# Servorino_FT230X_brick_super_tiny.net
KiCad netlist of a schematic drawn in EAGLE
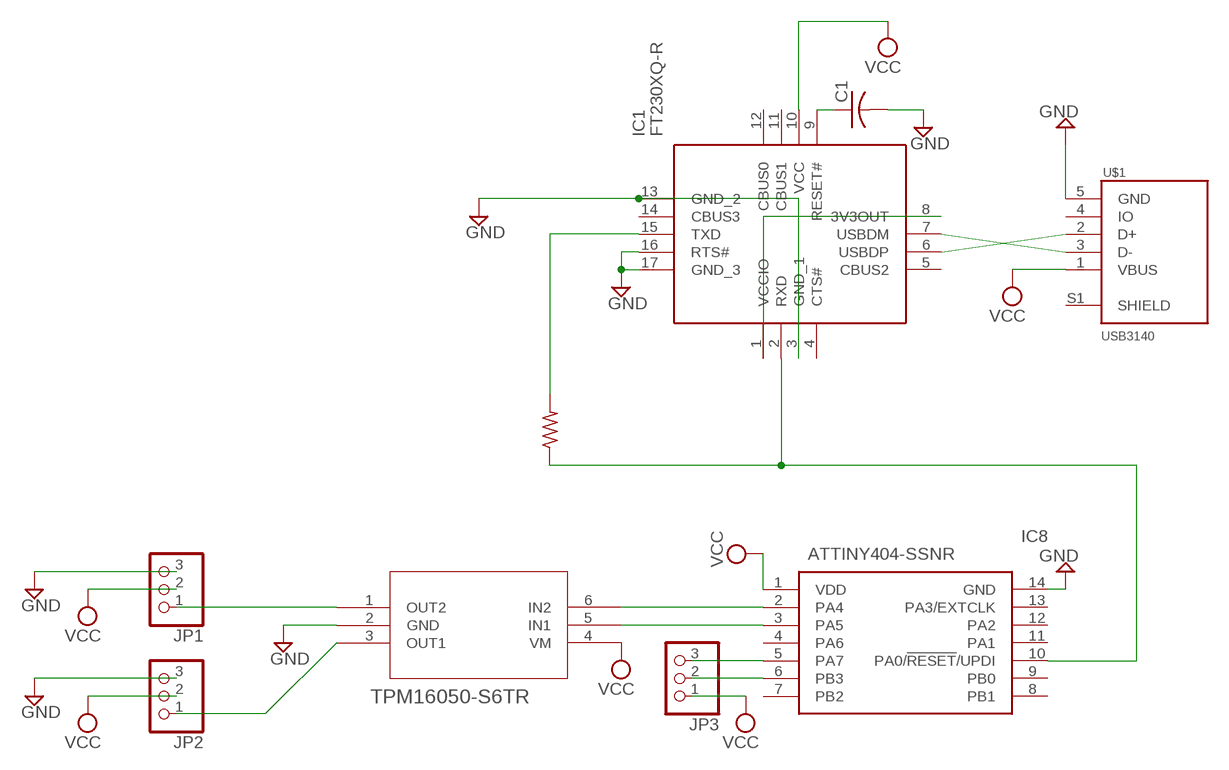
[diagram p0: schematic, sheet 1]

(export (version "E")
  (design (tool "Eeschema 10.0.6"))
  (components
    (comp (ref "C1")
      (value "C-USC0603")
      (footprint "eagle-import:C0603")
      (libsource (lib "eagle-import") (part "C-USC0603"))
    )
    (comp (ref "IC1")
      (value "FT230XQ-R")
      (footprint "eagle-import:QFN65P400X400X80-17N")
      (fields (field (name "MOUSER_PART_NUMBER") "895-FT230XQ-R"))
      (libsource (lib "eagle-import") (part "FT230XQ-R"))
    )
    (comp (ref "IC8")
      (value "ATTINY404-SSNR")
      (footprint "eagle-import:SOIC127P600X175-14N")
      (fields (field (name "MOUSER_PART_NUMBER") "556-ATTINY404-SSNR"))
      (libsource (lib "eagle-import") (part "ATTINY404-SSNR"))
    )
    (comp (ref "JP1")
      (value "PINHD-1X3")
      (footprint "eagle-import:1X03")
      (libsource (lib "eagle-import") (part "PINHD-1X3"))
    )
    (comp (ref "JP2")
      (value "PINHD-1X3")
      (footprint "eagle-import:1X03")
      (libsource (lib "eagle-import") (part "PINHD-1X3"))
    )
    (comp (ref "JP3")
      (value "PINHD-1X3")
      (footprint "eagle-import:1X03")
      (libsource (lib "eagle-import") (part "PINHD-1X3"))
    )
    (comp (ref "R6")
      (value "470")
      (footprint "eagle-import:R0805")
      (libsource (lib "eagle-import") (part "R-US_R0805"))
    )
    (comp (ref "U$1")
      (value "USB3140")
      (footprint "eagle-import:USB3140-30-0170-0-C")
      (libsource (lib "eagle-import") (part "USB3140"))
    )
    (comp (ref "U1")
      (value "TPM16050-S6TR")
      (footprint "eagle-import:SOT23-6_TPK")
      (fields (field (name "COPYRIGHT") "Copyright (C) 2025 Ultra Librarian. All rights reserved."))
      (libsource (lib "eagle-import") (part "TPM16050-S6TR"))
    )
  )
  (nets
    (net (code "1") (name "GND") (class "Default")
      (node (ref "C1") (pin "2") (pinfunction "2_2") (pintype "passive"))
      (node (ref "IC1") (pin "13") (pinfunction "GND_2_13") (pintype "bidirectional"))
      (node (ref "IC1") (pin "16") (pinfunction "RTS#_16") (pintype "bidirectional"))
      (node (ref "IC1") (pin "17") (pinfunction "GND_3_17") (pintype "bidirectional"))
      (node (ref "IC1") (pin "3") (pinfunction "GND_1_3") (pintype "bidirectional"))
      (node (ref "IC8") (pin "14") (pinfunction "GND_14") (pintype "bidirectional"))
      (node (ref "JP1") (pin "3") (pinfunction "3_3") (pintype "passive"))
      (node (ref "JP2") (pin "3") (pinfunction "3_3") (pintype "passive"))
      (node (ref "U$1") (pin "5") (pinfunction "GND_5") (pintype "passive"))
      (node (ref "U1") (pin "2") (pinfunction "GND_2") (pintype "passive"))
    )
    (net (code "2") (name "Net-(IC1-3V3OUT)") (class "Default")
      (node (ref "IC1") (pin "1") (pinfunction "VCCIO_1") (pintype "bidirectional"))
      (node (ref "IC1") (pin "8") (pinfunction "3V3OUT_8") (pintype "bidirectional"))
    )
    (net (code "3") (name "Net-(IC1-RESET#)") (class "Default")
      (node (ref "C1") (pin "1") (pinfunction "1_1") (pintype "passive"))
      (node (ref "IC1") (pin "9") (pinfunction "RESET#_9") (pintype "bidirectional"))
    )
    (net (code "4") (name "Net-(IC1-RXD)") (class "Default")
      (node (ref "IC1") (pin "2") (pinfunction "RXD_2") (pintype "bidirectional"))
      (node (ref "IC8") (pin "10") (pinfunction "PA0/~{RESET}/UPDI_10") (pintype "bidirectional"))
      (node (ref "R6") (pin "1") (pinfunction "1_1") (pintype "passive"))
    )
    (net (code "5") (name "Net-(IC1-TXD)") (class "Default")
      (node (ref "IC1") (pin "15") (pinfunction "TXD_15") (pintype "bidirectional"))
      (node (ref "R6") (pin "2") (pinfunction "2_2") (pintype "passive"))
    )
    (net (code "6") (name "Net-(IC1-USBDM)") (class "Default")
      (node (ref "IC1") (pin "7") (pinfunction "USBDM_7") (pintype "bidirectional"))
      (node (ref "U$1") (pin "3") (pinfunction "D-_3") (pintype "passive"))
    )
    (net (code "7") (name "Net-(IC1-USBDP)") (class "Default")
      (node (ref "IC1") (pin "6") (pinfunction "USBDP_6") (pintype "bidirectional"))
      (node (ref "U$1") (pin "2") (pinfunction "D+_2") (pintype "passive"))
    )
    (net (code "8") (name "Net-(IC8-PA4)") (class "Default")
      (node (ref "IC8") (pin "2") (pinfunction "PA4_2") (pintype "bidirectional"))
      (node (ref "U1") (pin "6") (pinfunction "IN2_6") (pintype "input"))
    )
    (net (code "9") (name "Net-(IC8-PA5)") (class "Default")
      (node (ref "IC8") (pin "3") (pinfunction "PA5_3") (pintype "bidirectional"))
      (node (ref "U1") (pin "5") (pinfunction "IN1_5") (pintype "input"))
    )
    (net (code "10") (name "Net-(IC8-PA7)") (class "Default")
      (node (ref "IC8") (pin "5") (pinfunction "PA7_5") (pintype "bidirectional"))
      (node (ref "JP3") (pin "3") (pinfunction "3_3") (pintype "passive"))
    )
    (net (code "11") (name "Net-(IC8-PB3)") (class "Default")
      (node (ref "IC8") (pin "6") (pinfunction "PB3_6") (pintype "bidirectional"))
      (node (ref "JP3") (pin "2") (pinfunction "2_2") (pintype "passive"))
    )
    (net (code "12") (name "Net-(U1-OUT1)") (class "Default")
      (node (ref "JP2") (pin "1") (pinfunction "1_1") (pintype "passive"))
      (node (ref "U1") (pin "3") (pinfunction "OUT1_3") (pintype "output"))
    )
    (net (code "13") (name "Net-(U1-OUT2)") (class "Default")
      (node (ref "JP1") (pin "1") (pinfunction "1_1") (pintype "passive"))
      (node (ref "U1") (pin "1") (pinfunction "OUT2_1") (pintype "output"))
    )
    (net (code "14") (name "VCC") (class "Default")
      (node (ref "IC1") (pin "10") (pinfunction "VCC_10") (pintype "bidirectional"))
      (node (ref "IC8") (pin "1") (pinfunction "VDD_1") (pintype "bidirectional"))
      (node (ref "JP1") (pin "2") (pinfunction "2_2") (pintype "passive"))
      (node (ref "JP2") (pin "2") (pinfunction "2_2") (pintype "passive"))
      (node (ref "JP3") (pin "1") (pinfunction "1_1") (pintype "passive"))
      (node (ref "U$1") (pin "1") (pinfunction "VBUS_1") (pintype "passive"))
      (node (ref "U1") (pin "4") (pinfunction "VM_4") (pintype "power_in"))
    )
    (net (code "15") (name "unconnected-(IC1-CBUS0-Pad12)") (class "Default")
      (node (ref "IC1") (pin "12") (pinfunction "CBUS0_12") (pintype "bidirectional"))
    )
    (net (code "16") (name "unconnected-(IC1-CBUS1-Pad11)") (class "Default")
      (node (ref "IC1") (pin "11") (pinfunction "CBUS1_11") (pintype "bidirectional"))
    )
    (net (code "17") (name "unconnected-(IC1-CBUS2-Pad5)") (class "Default")
      (node (ref "IC1") (pin "5") (pinfunction "CBUS2_5") (pintype "bidirectional"))
    )
    (net (code "18") (name "unconnected-(IC1-CBUS3-Pad14)") (class "Default")
      (node (ref "IC1") (pin "14") (pinfunction "CBUS3_14") (pintype "bidirectional"))
    )
    (net (code "19") (name "unconnected-(IC1-CTS#-Pad4)") (class "Default")
      (node (ref "IC1") (pin "4") (pinfunction "CTS#_4") (pintype "bidirectional"))
    )
    (net (code "20") (name "unconnected-(IC8-PA1-Pad11)") (class "Default")
      (node (ref "IC8") (pin "11") (pinfunction "PA1_11") (pintype "bidirectional"))
    )
    (net (code "21") (name "unconnected-(IC8-PA2-Pad12)") (class "Default")
      (node (ref "IC8") (pin "12") (pinfunction "PA2_12") (pintype "bidirectional"))
    )
    (net (code "22") (name "unconnected-(IC8-PA3{slash}EXTCLK-Pad13)") (class "Default")
      (node (ref "IC8") (pin "13") (pinfunction "PA3/EXTCLK_13") (pintype "bidirectional"))
    )
    (net (code "23") (name "unconnected-(IC8-PA6-Pad4)") (class "Default")
      (node (ref "IC8") (pin "4") (pinfunction "PA6_4") (pintype "bidirectional"))
    )
    (net (code "24") (name "unconnected-(IC8-PB0-Pad9)") (class "Default")
      (node (ref "IC8") (pin "9") (pinfunction "PB0_9") (pintype "bidirectional"))
    )
    (net (code "25") (name "unconnected-(IC8-PB1-Pad8)") (class "Default")
      (node (ref "IC8") (pin "8") (pinfunction "PB1_8") (pintype "bidirectional"))
    )
    (net (code "26") (name "unconnected-(IC8-PB2-Pad7)") (class "Default")
      (node (ref "IC8") (pin "7") (pinfunction "PB2_7") (pintype "bidirectional"))
    )
    (net (code "27") (name "unconnected-(U$1-IO-Pad4)") (class "Default")
      (node (ref "U$1") (pin "4") (pinfunction "IO_4") (pintype "passive"))
    )
    (net (code "28") (name "unconnected-(U$1-SHIELD-PadS1)") (class "Default")
      (node (ref "U$1") (pin "S1") (pinfunction "SHIELD_S1") (pintype "passive"))
    )
  )
)
